# PowerOut.net
KiCad netlist of a schematic drawn in EAGLE
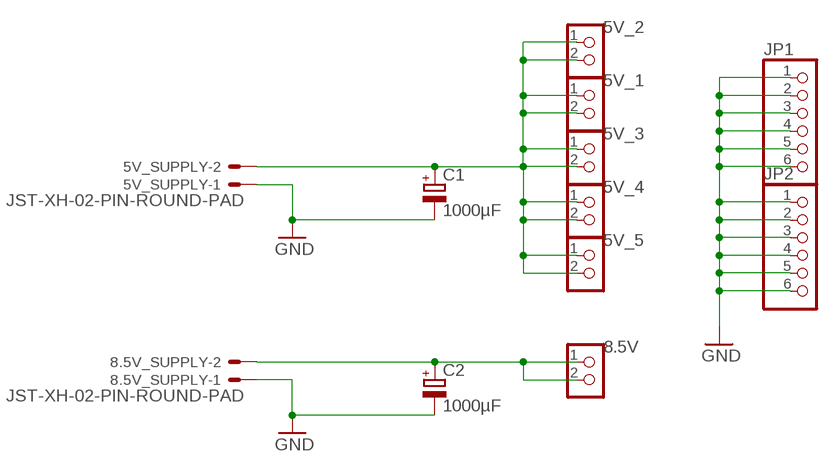
[diagram p0: schematic, sheet 1]

(export (version "E")
  (design (tool "Eeschema 10.0.6"))
  (components
    (comp (ref "5V_1")
      (value "CON_TERMINAL_BLOCK_02-5MM")
      (footprint "eagle-import:TERMINAL_BLOCK_2P_5")
      (libsource (lib "eagle-import") (part "CON_TERMINAL_BLOCK_02-5MM"))
    )
    (comp (ref "5V_2")
      (value "CON_TERMINAL_BLOCK_02-5MM")
      (footprint "eagle-import:TERMINAL_BLOCK_2P_5")
      (libsource (lib "eagle-import") (part "CON_TERMINAL_BLOCK_02-5MM"))
    )
    (comp (ref "5V_3")
      (value "CON_TERMINAL_BLOCK_02-5MM")
      (footprint "eagle-import:TERMINAL_BLOCK_2P_5")
      (libsource (lib "eagle-import") (part "CON_TERMINAL_BLOCK_02-5MM"))
    )
    (comp (ref "5V_4")
      (value "CON_TERMINAL_BLOCK_02-5MM")
      (footprint "eagle-import:TERMINAL_BLOCK_2P_5")
      (libsource (lib "eagle-import") (part "CON_TERMINAL_BLOCK_02-5MM"))
    )
    (comp (ref "5V_5")
      (value "CON_TERMINAL_BLOCK_02-5MM")
      (footprint "eagle-import:TERMINAL_BLOCK_2P_5")
      (libsource (lib "eagle-import") (part "CON_TERMINAL_BLOCK_02-5MM"))
    )
    (comp (ref "5V_SUPPLY")
      (value "JST-XH-02-PIN-ROUND-PAD")
      (footprint "eagle-import:JST-XH-02-PACKAGE-ROUND-PAD")
      (libsource (lib "eagle-import") (part "JST-XH-02-PIN-ROUND-PAD"))
    )
    (comp (ref "8.5V")
      (value "CON_TERMINAL_BLOCK_02-5MM")
      (footprint "eagle-import:TERMINAL_BLOCK_2P_5")
      (libsource (lib "eagle-import") (part "CON_TERMINAL_BLOCK_02-5MM"))
    )
    (comp (ref "8.5V_SUPPLY")
      (value "JST-XH-02-PIN-ROUND-PAD")
      (footprint "eagle-import:JST-XH-02-PACKAGE-ROUND-PAD")
      (libsource (lib "eagle-import") (part "JST-XH-02-PIN-ROUND-PAD"))
    )
    (comp (ref "C1")
      (value "1000µF")
      (footprint "eagle-import:E5-10,5")
      (libsource (lib "eagle-import") (part "CPOL-EUE5-10.5"))
    )
    (comp (ref "C2")
      (value "1000µF")
      (footprint "eagle-import:E5-10,5")
      (libsource (lib "eagle-import") (part "CPOL-EUE5-10.5"))
    )
    (comp (ref "JP1")
      (value "PINHD-1X6")
      (footprint "eagle-import:1X06")
      (libsource (lib "eagle-import") (part "PINHD-1X6"))
    )
    (comp (ref "JP2")
      (value "PINHD-1X6")
      (footprint "eagle-import:1X06")
      (libsource (lib "eagle-import") (part "PINHD-1X6"))
    )
  )
  (nets
    (net (code "1") (name "GND") (class "Default")
      (node (ref "5V_SUPPLY") (pin "1") (pinfunction "S_1") (pintype "passive"))
      (node (ref "8.5V_SUPPLY") (pin "1") (pinfunction "S_1") (pintype "passive"))
      (node (ref "C1") (pin "-") (pinfunction "-_-") (pintype "passive"))
      (node (ref "C2") (pin "-") (pinfunction "-_-") (pintype "passive"))
      (node (ref "JP1") (pin "1") (pinfunction "1_1") (pintype "passive"))
      (node (ref "JP1") (pin "2") (pinfunction "2_2") (pintype "passive"))
      (node (ref "JP1") (pin "3") (pinfunction "3_3") (pintype "passive"))
      (node (ref "JP1") (pin "4") (pinfunction "4_4") (pintype "passive"))
      (node (ref "JP1") (pin "5") (pinfunction "5_5") (pintype "passive"))
      (node (ref "JP1") (pin "6") (pinfunction "6_6") (pintype "passive"))
      (node (ref "JP2") (pin "1") (pinfunction "1_1") (pintype "passive"))
      (node (ref "JP2") (pin "2") (pinfunction "2_2") (pintype "passive"))
      (node (ref "JP2") (pin "3") (pinfunction "3_3") (pintype "passive"))
      (node (ref "JP2") (pin "4") (pinfunction "4_4") (pintype "passive"))
      (node (ref "JP2") (pin "5") (pinfunction "5_5") (pintype "passive"))
      (node (ref "JP2") (pin "6") (pinfunction "6_6") (pintype "passive"))
    )
    (net (code "2") (name "Net-(5V_SUPPLYB-S)") (class "Default")
      (node (ref "5V_1") (pin "1") (pinfunction "1_1") (pintype "passive"))
      (node (ref "5V_1") (pin "2") (pinfunction "2_2") (pintype "passive"))
      (node (ref "5V_2") (pin "1") (pinfunction "1_1") (pintype "passive"))
      (node (ref "5V_2") (pin "2") (pinfunction "2_2") (pintype "passive"))
      (node (ref "5V_3") (pin "1") (pinfunction "1_1") (pintype "passive"))
      (node (ref "5V_3") (pin "2") (pinfunction "2_2") (pintype "passive"))
      (node (ref "5V_4") (pin "1") (pinfunction "1_1") (pintype "passive"))
      (node (ref "5V_4") (pin "2") (pinfunction "2_2") (pintype "passive"))
      (node (ref "5V_5") (pin "1") (pinfunction "1_1") (pintype "passive"))
      (node (ref "5V_5") (pin "2") (pinfunction "2_2") (pintype "passive"))
      (node (ref "5V_SUPPLY") (pin "2") (pinfunction "S_2") (pintype "passive"))
      (node (ref "C1") (pin "+") (pinfunction "+_+") (pintype "passive"))
    )
    (net (code "3") (name "Net-(8.5V_SUPPLYB-S)") (class "Default")
      (node (ref "8.5V") (pin "1") (pinfunction "1_1") (pintype "passive"))
      (node (ref "8.5V") (pin "2") (pinfunction "2_2") (pintype "passive"))
      (node (ref "8.5V_SUPPLY") (pin "2") (pinfunction "S_2") (pintype "passive"))
      (node (ref "C2") (pin "+") (pinfunction "+_+") (pintype "passive"))
    )
  )
)
